# esquematicobluepill.net
KiCad netlist of a schematic drawn in Altium Designer
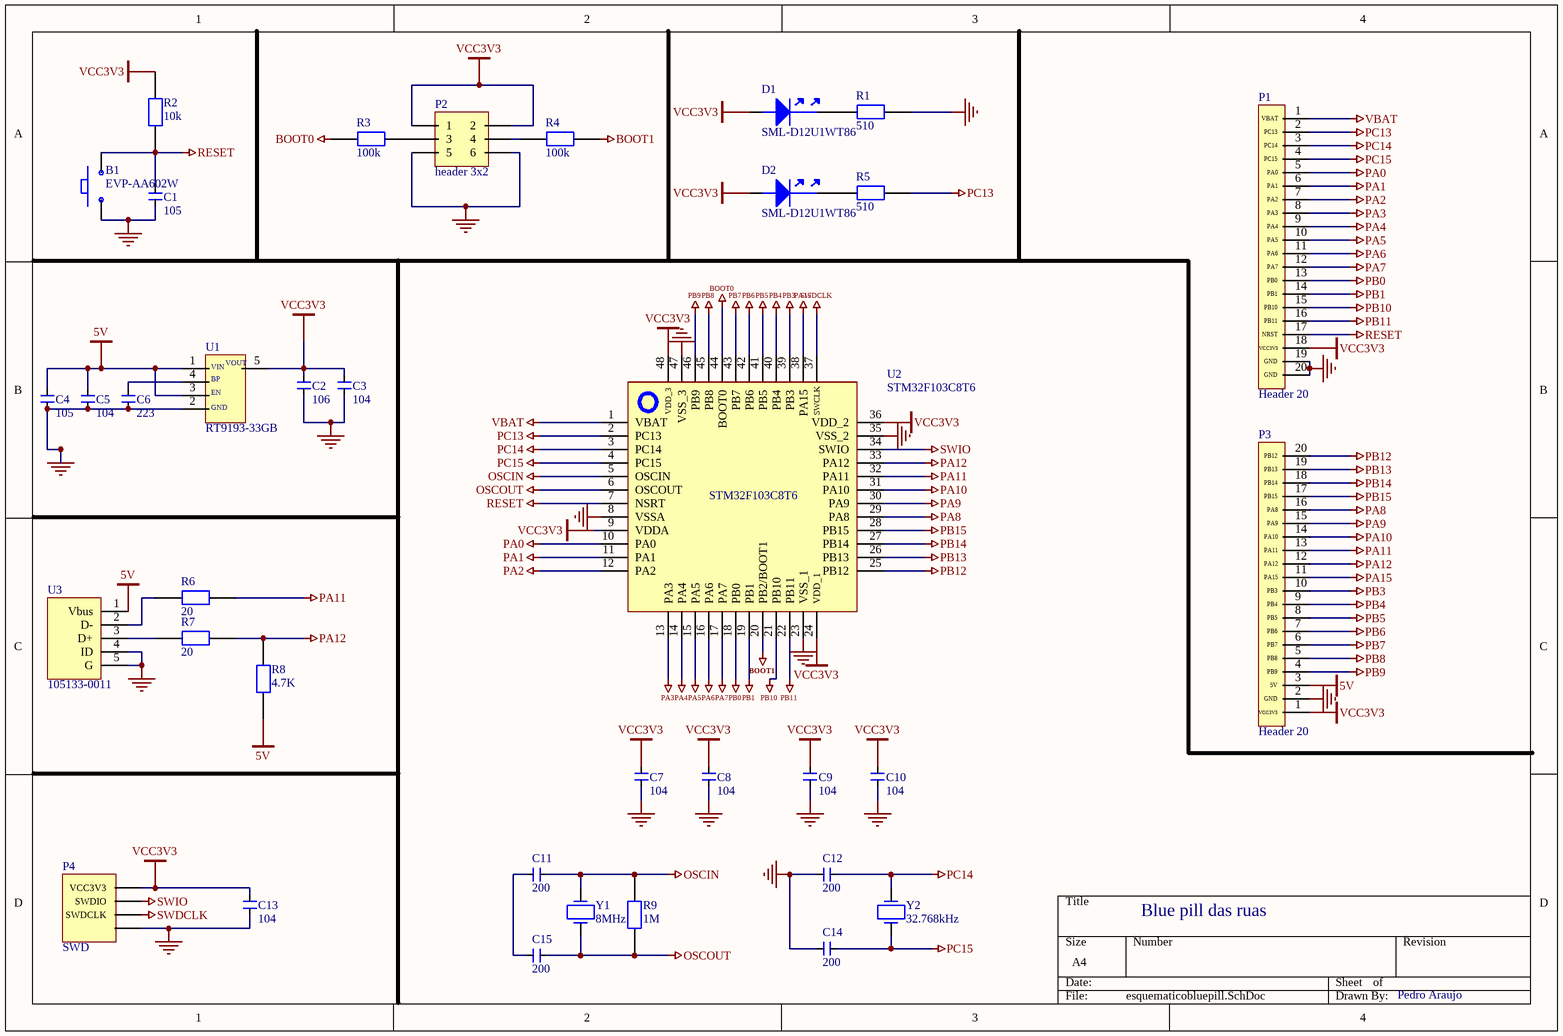
[diagram p0: esquematicobluepill.SchDoc]

(export (version "E")
  (design (tool "Eeschema 10.0.6"))
  (components
    (comp (ref "B1")
      (value "EVP-AA602W")
      (footprint "botao")
      (description "Switch Tactile N.O. SPST Rectangular Button J-Bend 0.02A 15VDC 3.5N SMD Embossed T/R")
      (fields (field (name "MANUFACTURER") "Panasonic"))
      (libsource (lib "bluepill") (part "EVP-AA602W"))
    )
    (comp (ref "C1")
      (value "105")
      (footprint "C_1µF_10V")
      (description "10V 1uF X7R ±10% 0603 Multilayer Ceramic Capacitors MLCC - SMD/SMT ROHS")
      (fields
        (field (name "MANUFACTURER") "Samsung Electro-Mechanics")
        (field (name "MANUFACTURER PART NUMBER") "CL10B105KP8NNNC")
      )
      (libsource (lib "bluepill") (part "CL10B105KP8NNNC"))
    )
    (comp (ref "C2")
      (value "106")
      (footprint "C_10µF_10V")
      (description "10V 10uF X5R ±10% 0603 Multilayer Ceramic Capacitors MLCC - SMD/SMT ROHS")
      (fields
        (field (name "MANUFACTURER") "Samsung Electro-Mechanics")
        (field (name "MANUFACTURER PART NUMBER") "CL10A106KP8NNNC")
      )
      (libsource (lib "bluepill") (part "CL10A106KP8NNNC"))
    )
    (comp (ref "C3")
      (value "104")
      (footprint "C_0603_0.1uF_10V")
      (description "10V 100nF X5R ±10% 0201 Multilayer Ceramic Capacitors MLCC - SMD/SMT ROHS")
      (fields
        (field (name "MANUFACTURER") "Samsung Electro-Mechanics")
        (field (name "MANUFACTURER PART NUMBER") "CL03A104KP3NNNC")
      )
      (libsource (lib "bluepill") (part "CL03A104KP3NNNC"))
    )
    (comp (ref "C4")
      (value "105")
      (footprint "C_1µF_10V")
      (description "10V 1uF X7R ±10% 0603 Multilayer Ceramic Capacitors MLCC - SMD/SMT ROHS")
      (fields
        (field (name "MANUFACTURER") "Samsung Electro-Mechanics")
        (field (name "MANUFACTURER PART NUMBER") "CL10B105KP8NNNC")
      )
      (libsource (lib "bluepill") (part "CL10B105KP8NNNC"))
    )
    (comp (ref "C5")
      (value "104")
      (footprint "C_0603_0.1uF_10V")
      (description "10V 100nF X5R ±10% 0201 Multilayer Ceramic Capacitors MLCC - SMD/SMT ROHS")
      (fields
        (field (name "MANUFACTURER") "Samsung Electro-Mechanics")
        (field (name "MANUFACTURER PART NUMBER") "CL03A104KP3NNNC")
      )
      (libsource (lib "bluepill") (part "CL03A104KP3NNNC"))
    )
    (comp (ref "C6")
      (value "223")
      (footprint "C_0.022 µF_10V")
      (description "Multilayer Ceramic Capacitor, 0.022 uF, 10 V, ± 10%, X5R, 0201 [0603 Metric]")
      (fields
        (field (name "MANUFACTURER") "Samsung Electro-Mechanics")
        (field (name "MANUFACTURER PART NUMBER") "CL03A223KP3NNNC")
      )
      (libsource (lib "bluepill") (part "CL03A223KP3NNNC"))
    )
    (comp (ref "C7")
      (value "104")
      (footprint "C_0603_0.1uF_10V")
      (description "10V 100nF X5R ±10% 0201 Multilayer Ceramic Capacitors MLCC - SMD/SMT ROHS")
      (fields
        (field (name "MANUFACTURER") "Samsung Electro-Mechanics")
        (field (name "MANUFACTURER PART NUMBER") "CL03A104KP3NNNC")
      )
      (libsource (lib "bluepill") (part "CL03A104KP3NNNC"))
    )
    (comp (ref "C8")
      (value "104")
      (footprint "C_0603_0.1uF_10V")
      (description "10V 100nF X5R ±10% 0201 Multilayer Ceramic Capacitors MLCC - SMD/SMT ROHS")
      (fields
        (field (name "MANUFACTURER") "Samsung Electro-Mechanics")
        (field (name "MANUFACTURER PART NUMBER") "CL03A104KP3NNNC")
      )
      (libsource (lib "bluepill") (part "CL03A104KP3NNNC"))
    )
    (comp (ref "C9")
      (value "104")
      (footprint "C_0603_0.1uF_10V")
      (description "10V 100nF X5R ±10% 0201 Multilayer Ceramic Capacitors MLCC - SMD/SMT ROHS")
      (fields
        (field (name "MANUFACTURER") "Samsung Electro-Mechanics")
        (field (name "MANUFACTURER PART NUMBER") "CL03A104KP3NNNC")
      )
      (libsource (lib "bluepill") (part "CL03A104KP3NNNC"))
    )
    (comp (ref "C10")
      (value "104")
      (footprint "C_0603_0.1uF_10V")
      (description "10V 100nF X5R ±10% 0201 Multilayer Ceramic Capacitors MLCC - SMD/SMT ROHS")
      (fields
        (field (name "MANUFACTURER") "Samsung Electro-Mechanics")
        (field (name "MANUFACTURER PART NUMBER") "CL03A104KP3NNNC")
      )
      (libsource (lib "bluepill") (part "CL03A104KP3NNNC"))
    )
    (comp (ref "C11")
      (value "200")
      (footprint "C_20pF_50V")
      (description "Cap Ceramic 20pF 50V C0G 5% Pad SMD 0603 125C Automotive T/R")
      (fields
        (field (name "MANUFACTURER") "Samsung Electro-Mechanics")
        (field (name "MANUFACTURER PART NUMBER") "CL10C200JB81PNC")
      )
      (libsource (lib "bluepill") (part "CL10C200JB81PNC"))
    )
    (comp (ref "C12")
      (value "200")
      (footprint "C_20pF_50V")
      (description "Cap Ceramic 20pF 50V C0G 5% Pad SMD 0603 125C Automotive T/R")
      (fields
        (field (name "MANUFACTURER") "Samsung Electro-Mechanics")
        (field (name "MANUFACTURER PART NUMBER") "CL10C200JB81PNC")
      )
      (libsource (lib "bluepill") (part "CL10C200JB81PNC"))
    )
    (comp (ref "C13")
      (value "104")
      (footprint "C_0603_0.1uF_10V")
      (description "10V 100nF X5R ±10% 0201 Multilayer Ceramic Capacitors MLCC - SMD/SMT ROHS")
      (fields
        (field (name "MANUFACTURER") "Samsung Electro-Mechanics")
        (field (name "MANUFACTURER PART NUMBER") "CL03A104KP3NNNC")
      )
      (libsource (lib "bluepill") (part "CL03A104KP3NNNC"))
    )
    (comp (ref "C14")
      (value "200")
      (footprint "C_20pF_50V")
      (description "Cap Ceramic 20pF 50V C0G 5% Pad SMD 0603 125C Automotive T/R")
      (fields
        (field (name "MANUFACTURER") "Samsung Electro-Mechanics")
        (field (name "MANUFACTURER PART NUMBER") "CL10C200JB81PNC")
      )
      (libsource (lib "bluepill") (part "CL10C200JB81PNC"))
    )
    (comp (ref "C15")
      (value "200")
      (footprint "C_20pF_50V")
      (description "Cap Ceramic 20pF 50V C0G 5% Pad SMD 0603 125C Automotive T/R")
      (fields
        (field (name "MANUFACTURER") "Samsung Electro-Mechanics")
        (field (name "MANUFACTURER PART NUMBER") "CL10C200JB81PNC")
      )
      (libsource (lib "bluepill") (part "CL10C200JB81PNC"))
    )
    (comp (ref "D1")
      (value "SML-D12U1WT86")
      (footprint "Led_0603_red")
      (description "LED Uni-Color Red 2-Pin Chip 0603(1608Metric) T/R")
      (fields (field (name "MANUFACTURER") "ROHM"))
      (libsource (lib "bluepill") (part "SML-D12U1WT86"))
    )
    (comp (ref "D2")
      (value "SML-D12U1WT86")
      (footprint "Led_0603_red")
      (description "LED Uni-Color Red 2-Pin Chip 0603(1608Metric) T/R")
      (fields (field (name "MANUFACTURER") "ROHM"))
      (libsource (lib "bluepill") (part "SML-D12U1WT86"))
    )
    (comp (ref "P1")
      (value "Header 20")
      (footprint "20pin")
      (description "KK 254 Breakaway Header, Vertical, 20 Circuits, Tin (Sn) Plating, Mating Pin Length 6.09mm")
      (fields (field (name "MANUFACTURER") "Molex") (field (name "MANUFACTURER PART NUMBER") "22-28-4200"))
      (libsource (lib "bluepill") (part "22-28-4200 p3"))
    )
    (comp (ref "P2")
      (value "header 3x2")
      (footprint "HEADER3X2")
      (description "Conn Unshrouded Header HDR 6 POS 2.54mm Solder ST Top Entry SMD C-Grid Bag")
      (fields (field (name "MANUFACTURER") "Molex") (field (name "MANUFACTURER PART NUMBER") "15-91-2060"))
      (libsource (lib "bluepill") (part "15-91-2060"))
    )
    (comp (ref "P3")
      (value "Header 20")
      (footprint "20pin")
      (description "KK 254 Breakaway Header, Vertical, 20 Circuits, Tin (Sn) Plating, Mating Pin Length 6.09mm")
      (fields (field (name "MANUFACTURER") "Molex") (field (name "MANUFACTURER PART NUMBER") "22-28-4200"))
      (libsource (lib "bluepill") (part "22-28-4200 p4"))
    )
    (comp (ref "P4")
      (value "SWD")
      (footprint "22-05-2041")
      (description "KK 254 Wire-to-Board Header Single Row 90° 4 Circuits PA Polyamide Nylon Tin Plating")
      (fields (field (name "MANUFACTURER") "Molex") (field (name "MANUFACTURER PART NUMBER") "22-05-2041"))
      (libsource (lib "bluepill") (part "22-05-2041"))
    )
    (comp (ref "R1")
      (value "510")
      (footprint "R_0603_510")
      (description "Res Thick Film 0603 510 Ohm 1% 0.25W(1/4W) +/-100ppm/C Molded SMD Automotive Punched T/R")
      (fields
        (field (name "MANUFACTURER") "Panasonic")
        (field (name "MANUFACTURER PART NUMBER") "ERJ-PA3F5100V")
      )
      (libsource (lib "bluepill") (part "ERJ-PA3F5100V"))
    )
    (comp (ref "R2")
      (value "10k")
      (footprint "R_0603_10K")
      (description "Res Thick Film 0603 10K Ohm 1% 0.25W(1/4W) ±100ppm/C Pad SMD Automotive T/R")
      (fields
        (field (name "MANUFACTURER") "Panasonic")
        (field (name "MANUFACTURER PART NUMBER") "ERJPA3F1002V")
      )
      (libsource (lib "bluepill") (part "ERJPA3F1002V"))
    )
    (comp (ref "R3")
      (value "100k")
      (footprint "R_0603_100K")
      (description "Resistor Thick Film 0603 100K Ohm 1% 1/10W 100ppm/C Molded SMD Punched Carrier T/R")
      (fields
        (field (name "MANUFACTURER") "Panasonic")
        (field (name "MANUFACTURER PART NUMBER") "ERJ-3EKF1003V")
      )
      (libsource (lib "bluepill") (part "ERJ-3EKF1003V"))
    )
    (comp (ref "R4")
      (value "100k")
      (footprint "R_0603_100K")
      (description "Resistor Thick Film 0603 100K Ohm 1% 1/10W 100ppm/C Molded SMD Punched Carrier T/R")
      (fields
        (field (name "MANUFACTURER") "Panasonic")
        (field (name "MANUFACTURER PART NUMBER") "ERJ-3EKF1003V")
      )
      (libsource (lib "bluepill") (part "ERJ-3EKF1003V"))
    )
    (comp (ref "R5")
      (value "510")
      (footprint "R_0603_510")
      (description "Res Thick Film 0603 510 Ohm 1% 0.25W(1/4W) +/-100ppm/C Molded SMD Automotive Punched T/R")
      (fields
        (field (name "MANUFACTURER") "Panasonic")
        (field (name "MANUFACTURER PART NUMBER") "ERJ-PA3F5100V")
      )
      (libsource (lib "bluepill") (part "ERJ-PA3F5100V"))
    )
    (comp (ref "R6")
      (value "20")
      (footprint "R_0603_20")
      (description "Res Thick Film 0603 20 Ohm 1% 0.25W(1/4W) ±100ppm/C Molded SMD Automotive Punched T/R")
      (fields
        (field (name "MANUFACTURER") "Panasonic")
        (field (name "MANUFACTURER PART NUMBER") "ERJPA3F20R0V")
      )
      (libsource (lib "bluepill") (part "ERJPA3F20R0V"))
    )
    (comp (ref "R7")
      (value "20")
      (footprint "R_0603_20")
      (description "Res Thick Film 0603 20 Ohm 1% 0.25W(1/4W) ±100ppm/C Molded SMD Automotive Punched T/R")
      (fields
        (field (name "MANUFACTURER") "Panasonic")
        (field (name "MANUFACTURER PART NUMBER") "ERJPA3F20R0V")
      )
      (libsource (lib "bluepill") (part "ERJPA3F20R0V"))
    )
    (comp (ref "R8")
      (value "4.7K")
      (footprint "R_0603_4.7K")
      (description "Res Thick Film 0603 4.7K Ohm 1% 0.25W(1/4W) ±100ppm/C Pad SMD Automotive T/R")
      (fields
        (field (name "MANUFACTURER") "Panasonic")
        (field (name "MANUFACTURER PART NUMBER") "ERJ-PA3F4701V")
      )
      (libsource (lib "bluepill") (part "ERJ-PA3F4701V"))
    )
    (comp (ref "R9")
      (value "1M")
      (footprint "R_0603_1M")
      (description "Res Thick Film 0603 1M Ohm 1% 0.25W(1/4W) ±100ppm/C Pad SMD Automotive T/R")
      (fields
        (field (name "MANUFACTURER") "Panasonic")
        (field (name "MANUFACTURER PART NUMBER") "ERJ-PA3F1004V")
      )
      (libsource (lib "bluepill") (part "ERJ-PA3F1004V"))
    )
    (comp (ref "U1")
      (value "RT9193-33GB")
      (footprint "SOT94P279X129-5N")
      (description "RT9193 Series 300 mA 3.3 V Ultra-Low Noise Ultra-Fast CMOS LDO Regulator-SC-70-5")
      (fields (field (name "MANUFACTURER") "Richtek"))
      (libsource (lib "bluepill") (part "RT9193-33GB"))
    )
    (comp (ref "U2")
      (value "STM32F103C8T6")
      (footprint "STM32F103C8T6")
      (description "MCU 32-bit STM32F1 ARM Cortex M3 RISC 64KB Flash 2.5V/3.3V 48-Pin LQFP Tray")
      (fields (field (name "MANUFACTURER") "STMicroelectronics"))
      (libsource (lib "bluepill") (part "STM32F103C8T6"))
    )
    (comp (ref "U3")
      (value "105133-0011")
      (footprint "usb")
      (description "Conn Micro USB 2.0 Type B RCP 5 POS 0.65mm Solder ST SMD 5 Terminal 1 Port Micro-USB T/R")
      (fields (field (name "MANUFACTURER") "Molex"))
      (libsource (lib "bluepill") (part "105133-0011"))
    )
    (comp (ref "Y1")
      (value "8MHz")
      (footprint "CRYSTAL_8MHZ")
      (description "Crystal 8MHz ±30ppm (Tol) ±50ppm (Stability) 20pF FUND 80Ohm 2-Pin HC-49/SDLF SMD T/R")
      (fields
        (field (name "MANUFACTURER") "Fox Electronics")
        (field (name "MANUFACTURER PART NUMBER") "FC4SDCBMF8.0-T1")
      )
      (libsource (lib "bluepill") (part "FC4SDCBMF8.0-T1"))
    )
    (comp (ref "Y2")
      (value "32.768kHz")
      (footprint "CRYSTAL_32.7680kHz")
      (description "Crystal, 32.7680KHZ, 12.5PF SMD, 2.0 X 1.2 x 0.6 mm, ABS06 Series ¦ Abracon ABS06-32.768KHz-1-T")
      (fields
        (field (name "MANUFACTURER") "Abracon")
        (field (name "MANUFACTURER PART NUMBER") "ABS06-32.768KHZ-1-T")
      )
      (libsource (lib "bluepill") (part "ABS06-32.768KHZ-1-T"))
    )
  )
  (nets
    (net (code "1") (name "5V") (class "Default")
      (node (ref "C4") (pin "1") (pinfunction "1_1") (pintype "passive"))
      (node (ref "C5") (pin "1") (pinfunction "1_1") (pintype "passive"))
      (node (ref "P3") (pin "3") (pinfunction "5V_3") (pintype "passive"))
      (node (ref "R8") (pin "2") (pinfunction "2_2") (pintype "passive"))
      (node (ref "U1") (pin "1") (pinfunction "1_1") (pintype "passive"))
      (node (ref "U1") (pin "3") (pinfunction "3_3") (pintype "passive"))
      (node (ref "U3") (pin "1") (pinfunction "Vbus_1") (pintype "passive"))
    )
    (net (code "2") (name "BOOT0") (class "Default")
      (node (ref "R3") (pin "1") (pinfunction "1_1") (pintype "passive"))
      (node (ref "U2") (pin "44") (pinfunction "BOOT0_44") (pintype "passive"))
    )
    (net (code "3") (name "BOOT1") (class "Default")
      (node (ref "R4") (pin "2") (pinfunction "2_2") (pintype "passive"))
      (node (ref "U2") (pin "20") (pinfunction "PB2/BOOT1_20") (pintype "passive"))
    )
    (net (code "4") (name "GND") (class "Default")
      (node (ref "B1") (pin "2") (pinfunction "2_2") (pintype "passive"))
      (node (ref "C1") (pin "2") (pinfunction "2_2") (pintype "passive"))
      (node (ref "C10") (pin "2") (pinfunction "2_2") (pintype "passive"))
      (node (ref "C12") (pin "1") (pinfunction "1_1") (pintype "passive"))
      (node (ref "C13") (pin "2") (pinfunction "2_2") (pintype "passive"))
      (node (ref "C14") (pin "1") (pinfunction "1_1") (pintype "passive"))
      (node (ref "C2") (pin "2") (pinfunction "2_2") (pintype "passive"))
      (node (ref "C3") (pin "2") (pinfunction "2_2") (pintype "passive"))
      (node (ref "C4") (pin "2") (pinfunction "2_2") (pintype "passive"))
      (node (ref "C5") (pin "2") (pinfunction "2_2") (pintype "passive"))
      (node (ref "C6") (pin "2") (pinfunction "2_2") (pintype "passive"))
      (node (ref "C7") (pin "2") (pinfunction "2_2") (pintype "passive"))
      (node (ref "C8") (pin "2") (pinfunction "2_2") (pintype "passive"))
      (node (ref "C9") (pin "2") (pinfunction "2_2") (pintype "passive"))
      (node (ref "P1") (pin "19") (pinfunction "GND_19") (pintype "passive"))
      (node (ref "P1") (pin "20") (pinfunction "GND_20") (pintype "passive"))
      (node (ref "P2") (pin "5") (pinfunction "5_5") (pintype "passive"))
      (node (ref "P2") (pin "6") (pinfunction "6_6") (pintype "passive"))
      (node (ref "P3") (pin "2") (pinfunction "GND_2") (pintype "passive"))
      (node (ref "P4") (pin "4") (pintype "passive"))
      (node (ref "R1") (pin "2") (pinfunction "2_2") (pintype "passive"))
      (node (ref "U1") (pin "2") (pinfunction "2_2") (pintype "passive"))
      (node (ref "U2") (pin "23") (pinfunction "VSS_1_23") (pintype "passive"))
      (node (ref "U2") (pin "35") (pinfunction "VSS_2_35") (pintype "passive"))
      (node (ref "U2") (pin "47") (pinfunction "VSS_3_47") (pintype "passive"))
      (node (ref "U2") (pin "8") (pinfunction "VSSA_8") (pintype "passive"))
      (node (ref "U3") (pin "4") (pinfunction "ID_4") (pintype "passive"))
      (node (ref "U3") (pin "5") (pinfunction "G_5") (pintype "passive"))
    )
    (net (code "5") (name "Net-(C6-Pad1)") (class "Default")
      (node (ref "C6") (pin "1") (pinfunction "1_1") (pintype "passive"))
      (node (ref "U1") (pin "4") (pinfunction "4_4") (pintype "passive"))
    )
    (net (code "6") (name "Net-(C11-Pad1)") (class "Default")
      (node (ref "C11") (pin "1") (pinfunction "1_1") (pintype "passive"))
      (node (ref "C15") (pin "1") (pinfunction "1_1") (pintype "passive"))
    )
    (net (code "7") (name "Net-(D1-Pad1)") (class "Default")
      (node (ref "D1") (pin "1") (pinfunction "1_1") (pintype "passive"))
      (node (ref "R1") (pin "1") (pinfunction "1_1") (pintype "passive"))
    )
    (net (code "8") (name "Net-(D2-Pad1)") (class "Default")
      (node (ref "D2") (pin "1") (pinfunction "1_1") (pintype "passive"))
      (node (ref "R5") (pin "1") (pinfunction "1_1") (pintype "passive"))
    )
    (net (code "9") (name "Net-(P2-Pad3)") (class "Default")
      (node (ref "P2") (pin "3") (pinfunction "3_3") (pintype "passive"))
      (node (ref "R3") (pin "2") (pinfunction "2_2") (pintype "passive"))
    )
    (net (code "10") (name "Net-(P2-Pad4)") (class "Default")
      (node (ref "P2") (pin "4") (pinfunction "4_4") (pintype "passive"))
      (node (ref "R4") (pin "1") (pinfunction "1_1") (pintype "passive"))
    )
    (net (code "11") (name "Net-(U3-D+)") (class "Default")
      (node (ref "R7") (pin "1") (pinfunction "1_1") (pintype "passive"))
      (node (ref "U3") (pin "3") (pinfunction "D+_3") (pintype "passive"))
    )
    (net (code "12") (name "Net-(U3-D-)") (class "Default")
      (node (ref "R6") (pin "1") (pinfunction "1_1") (pintype "passive"))
      (node (ref "U3") (pin "2") (pinfunction "D-_2") (pintype "passive"))
    )
    (net (code "13") (name "OSCIN") (class "Default")
      (node (ref "C11") (pin "2") (pinfunction "2_2") (pintype "passive"))
      (node (ref "R9") (pin "2") (pinfunction "2_2") (pintype "passive"))
      (node (ref "U2") (pin "5") (pinfunction "OSCIN_5") (pintype "passive"))
      (node (ref "Y1") (pin "1") (pinfunction "1_1") (pintype "passive"))
    )
    (net (code "14") (name "OSCOUT") (class "Default")
      (node (ref "C15") (pin "2") (pinfunction "2_2") (pintype "passive"))
      (node (ref "R9") (pin "1") (pinfunction "1_1") (pintype "passive"))
      (node (ref "U2") (pin "6") (pinfunction "OSCOUT_6") (pintype "passive"))
      (node (ref "Y1") (pin "2") (pinfunction "2_2") (pintype "passive"))
    )
    (net (code "15") (name "PA0") (class "Default")
      (node (ref "P1") (pin "5") (pinfunction "PA0_5") (pintype "passive"))
      (node (ref "U2") (pin "10") (pinfunction "PA0_10") (pintype "passive"))
    )
    (net (code "16") (name "PA1") (class "Default")
      (node (ref "P1") (pin "6") (pinfunction "PA1_6") (pintype "passive"))
      (node (ref "U2") (pin "11") (pinfunction "PA1_11") (pintype "passive"))
    )
    (net (code "17") (name "PA2") (class "Default")
      (node (ref "P1") (pin "7") (pinfunction "PA2_7") (pintype "passive"))
      (node (ref "U2") (pin "12") (pinfunction "PA2_12") (pintype "passive"))
    )
    (net (code "18") (name "PA3") (class "Default")
      (node (ref "P1") (pin "8") (pinfunction "PA3_8") (pintype "passive"))
      (node (ref "U2") (pin "13") (pinfunction "PA3_13") (pintype "passive"))
    )
    (net (code "19") (name "PA4") (class "Default")
      (node (ref "P1") (pin "9") (pinfunction "PA4_9") (pintype "passive"))
      (node (ref "U2") (pin "14") (pinfunction "PA4_14") (pintype "passive"))
    )
    (net (code "20") (name "PA5") (class "Default")
      (node (ref "P1") (pin "10") (pinfunction "PA5_10") (pintype "passive"))
      (node (ref "U2") (pin "15") (pinfunction "PA5_15") (pintype "passive"))
    )
    (net (code "21") (name "PA6") (class "Default")
      (node (ref "P1") (pin "11") (pinfunction "PA6_11") (pintype "passive"))
      (node (ref "U2") (pin "16") (pinfunction "PA6_16") (pintype "passive"))
    )
    (net (code "22") (name "PA7") (class "Default")
      (node (ref "P1") (pin "12") (pinfunction "PA7_12") (pintype "passive"))
      (node (ref "U2") (pin "17") (pinfunction "PA7_17") (pintype "passive"))
    )
    (net (code "23") (name "PA8") (class "Default")
      (node (ref "P3") (pin "16") (pinfunction "PA8_16") (pintype "passive"))
      (node (ref "U2") (pin "29") (pinfunction "PA8_29") (pintype "passive"))
    )
    (net (code "24") (name "PA9") (class "Default")
      (node (ref "P3") (pin "15") (pinfunction "PA9_15") (pintype "passive"))
      (node (ref "U2") (pin "30") (pinfunction "PA9_30") (pintype "passive"))
    )
    (net (code "25") (name "PA10") (class "Default")
      (node (ref "P3") (pin "14") (pinfunction "PA10_14") (pintype "passive"))
      (node (ref "U2") (pin "31") (pinfunction "PA10_31") (pintype "passive"))
    )
    (net (code "26") (name "PA11") (class "Default")
      (node (ref "P3") (pin "13") (pinfunction "PA11_13") (pintype "passive"))
      (node (ref "R6") (pin "2") (pinfunction "2_2") (pintype "passive"))
      (node (ref "U2") (pin "32") (pinfunction "PA11_32") (pintype "passive"))
    )
    (net (code "27") (name "PA12") (class "Default")
      (node (ref "P3") (pin "12") (pinfunction "PA12_12") (pintype "passive"))
      (node (ref "R7") (pin "2") (pinfunction "2_2") (pintype "passive"))
      (node (ref "R8") (pin "1") (pinfunction "1_1") (pintype "passive"))
      (node (ref "U2") (pin "33") (pinfunction "PA12_33") (pintype "passive"))
    )
    (net (code "28") (name "PA15") (class "Default")
      (node (ref "P3") (pin "11") (pinfunction "PA15_11") (pintype "passive"))
      (node (ref "U2") (pin "38") (pinfunction "PA15_38") (pintype "passive"))
    )
    (net (code "29") (name "PB0") (class "Default")
      (node (ref "P1") (pin "13") (pinfunction "PB0_13") (pintype "passive"))
      (node (ref "U2") (pin "18") (pinfunction "PB0_18") (pintype "passive"))
    )
    (net (code "30") (name "PB1") (class "Default")
      (node (ref "P1") (pin "14") (pinfunction "PB1_14") (pintype "passive"))
      (node (ref "U2") (pin "19") (pinfunction "PB1_19") (pintype "passive"))
    )
    (net (code "31") (name "PB3") (class "Default")
      (node (ref "P3") (pin "10") (pinfunction "PB3_10") (pintype "passive"))
      (node (ref "U2") (pin "39") (pinfunction "PB3_39") (pintype "passive"))
    )
    (net (code "32") (name "PB4") (class "Default")
      (node (ref "P3") (pin "9") (pinfunction "PB4_9") (pintype "passive"))
      (node (ref "U2") (pin "40") (pinfunction "PB4_40") (pintype "passive"))
    )
    (net (code "33") (name "PB5") (class "Default")
      (node (ref "P3") (pin "8") (pinfunction "PB5_8") (pintype "passive"))
      (node (ref "U2") (pin "41") (pinfunction "PB5_41") (pintype "passive"))
    )
    (net (code "34") (name "PB6") (class "Default")
      (node (ref "P3") (pin "7") (pinfunction "PB6_7") (pintype "passive"))
      (node (ref "U2") (pin "42") (pinfunction "PB6_42") (pintype "passive"))
    )
    (net (code "35") (name "PB7") (class "Default")
      (node (ref "P3") (pin "6") (pinfunction "PB7_6") (pintype "passive"))
      (node (ref "U2") (pin "43") (pinfunction "PB7_43") (pintype "passive"))
    )
    (net (code "36") (name "PB8") (class "Default")
      (node (ref "P3") (pin "5") (pinfunction "PB8_5") (pintype "passive"))
      (node (ref "U2") (pin "45") (pinfunction "PB8_45") (pintype "passive"))
    )
    (net (code "37") (name "PB9") (class "Default")
      (node (ref "P3") (pin "4") (pinfunction "PB9_4") (pintype "passive"))
      (node (ref "U2") (pin "46") (pinfunction "PB9_46") (pintype "passive"))
    )
    (net (code "38") (name "PB10") (class "Default")
      (node (ref "P1") (pin "15") (pinfunction "PB10_15") (pintype "passive"))
      (node (ref "U2") (pin "21") (pinfunction "PB10_21") (pintype "passive"))
    )
    (net (code "39") (name "PB11") (class "Default")
      (node (ref "P1") (pin "16") (pinfunction "PB11_16") (pintype "passive"))
      (node (ref "U2") (pin "22") (pinfunction "PB11_22") (pintype "passive"))
    )
    (net (code "40") (name "PB12") (class "Default")
      (node (ref "P3") (pin "20") (pinfunction "PB12_20") (pintype "passive"))
      (node (ref "U2") (pin "25") (pinfunction "PB12_25") (pintype "passive"))
    )
    (net (code "41") (name "PB13") (class "Default")
      (node (ref "P3") (pin "19") (pinfunction "PB13_19") (pintype "passive"))
      (node (ref "U2") (pin "26") (pinfunction "PB13_26") (pintype "passive"))
    )
    (net (code "42") (name "PB14") (class "Default")
      (node (ref "P3") (pin "18") (pinfunction "PB14_18") (pintype "passive"))
      (node (ref "U2") (pin "27") (pinfunction "PB14_27") (pintype "passive"))
    )
    (net (code "43") (name "PB15") (class "Default")
      (node (ref "P3") (pin "17") (pinfunction "PB15_17") (pintype "passive"))
      (node (ref "U2") (pin "28") (pinfunction "PB15_28") (pintype "passive"))
    )
    (net (code "44") (name "PC13") (class "Default")
      (node (ref "P1") (pin "2") (pinfunction "PC13_2") (pintype "passive"))
      (node (ref "R5") (pin "2") (pinfunction "2_2") (pintype "passive"))
      (node (ref "U2") (pin "2") (pinfunction "PC13_2") (pintype "passive"))
    )
    (net (code "45") (name "PC14") (class "Default")
      (node (ref "C12") (pin "2") (pinfunction "2_2") (pintype "passive"))
      (node (ref "P1") (pin "3") (pinfunction "PC14_3") (pintype "passive"))
      (node (ref "U2") (pin "3") (pinfunction "PC14_3") (pintype "passive"))
      (node (ref "Y2") (pin "1") (pinfunction "1_1") (pintype "passive"))
    )
    (net (code "46") (name "PC15") (class "Default")
      (node (ref "C14") (pin "2") (pinfunction "2_2") (pintype "passive"))
      (node (ref "P1") (pin "4") (pinfunction "PC15_4") (pintype "passive"))
      (node (ref "U2") (pin "4") (pinfunction "PC15_4") (pintype "passive"))
      (node (ref "Y2") (pin "2") (pinfunction "2_2") (pintype "passive"))
    )
    (net (code "47") (name "RESET") (class "Default")
      (node (ref "B1") (pin "1") (pinfunction "1_1") (pintype "passive"))
      (node (ref "C1") (pin "1") (pinfunction "1_1") (pintype "passive"))
      (node (ref "P1") (pin "17") (pinfunction "NRST_17") (pintype "passive"))
      (node (ref "R2") (pin "1") (pinfunction "1_1") (pintype "passive"))
      (node (ref "U2") (pin "7") (pinfunction "NSRT_7") (pintype "passive"))
    )
    (net (code "48") (name "SWDCLK") (class "Default")
      (node (ref "P4") (pin "3") (pinfunction "SWDCLK_3") (pintype "passive"))
      (node (ref "U2") (pin "37") (pinfunction "SWCLK_37") (pintype "passive"))
    )
    (net (code "49") (name "SWIO") (class "Default")
      (node (ref "P4") (pin "2") (pinfunction "SWDIO_2") (pintype "passive"))
      (node (ref "U2") (pin "34") (pinfunction "SWIO_34") (pintype "passive"))
    )
    (net (code "50") (name "VBAT") (class "Default")
      (node (ref "P1") (pin "1") (pinfunction "VBAT_1") (pintype "passive"))
      (node (ref "U2") (pin "1") (pinfunction "VBAT_1") (pintype "passive"))
    )
    (net (code "51") (name "VCC3V3") (class "Default")
      (node (ref "C10") (pin "1") (pinfunction "1_1") (pintype "passive"))
      (node (ref "C13") (pin "1") (pinfunction "1_1") (pintype "passive"))
      (node (ref "C2") (pin "1") (pinfunction "1_1") (pintype "passive"))
      (node (ref "C3") (pin "1") (pinfunction "1_1") (pintype "passive"))
      (node (ref "C7") (pin "1") (pinfunction "1_1") (pintype "passive"))
      (node (ref "C8") (pin "1") (pinfunction "1_1") (pintype "passive"))
      (node (ref "C9") (pin "1") (pinfunction "1_1") (pintype "passive"))
      (node (ref "D1") (pin "2") (pinfunction "2_2") (pintype "passive"))
      (node (ref "D2") (pin "2") (pinfunction "2_2") (pintype "passive"))
      (node (ref "P1") (pin "18") (pinfunction "VCC3V3_18") (pintype "passive"))
      (node (ref "P2") (pin "1") (pinfunction "1_1") (pintype "passive"))
      (node (ref "P2") (pin "2") (pinfunction "2_2") (pintype "passive"))
      (node (ref "P3") (pin "1") (pinfunction "VCC3V3_1") (pintype "passive"))
      (node (ref "P4") (pin "1") (pinfunction "VCC3V3_1") (pintype "passive"))
      (node (ref "R2") (pin "2") (pinfunction "2_2") (pintype "passive"))
      (node (ref "U1") (pin "5") (pinfunction "5_5") (pintype "passive"))
      (node (ref "U2") (pin "24") (pinfunction "VDD_1_24") (pintype "passive"))
      (node (ref "U2") (pin "36") (pinfunction "VDD_2_36") (pintype "passive"))
      (node (ref "U2") (pin "48") (pinfunction "VDD_3_48") (pintype "passive"))
      (node (ref "U2") (pin "9") (pinfunction "VDDA_9") (pintype "passive"))
    )
  )
)
